# PSPS_AVNC_SRD_central-2020-10-12-2.net
KiCad netlist of a schematic drawn in EAGLE
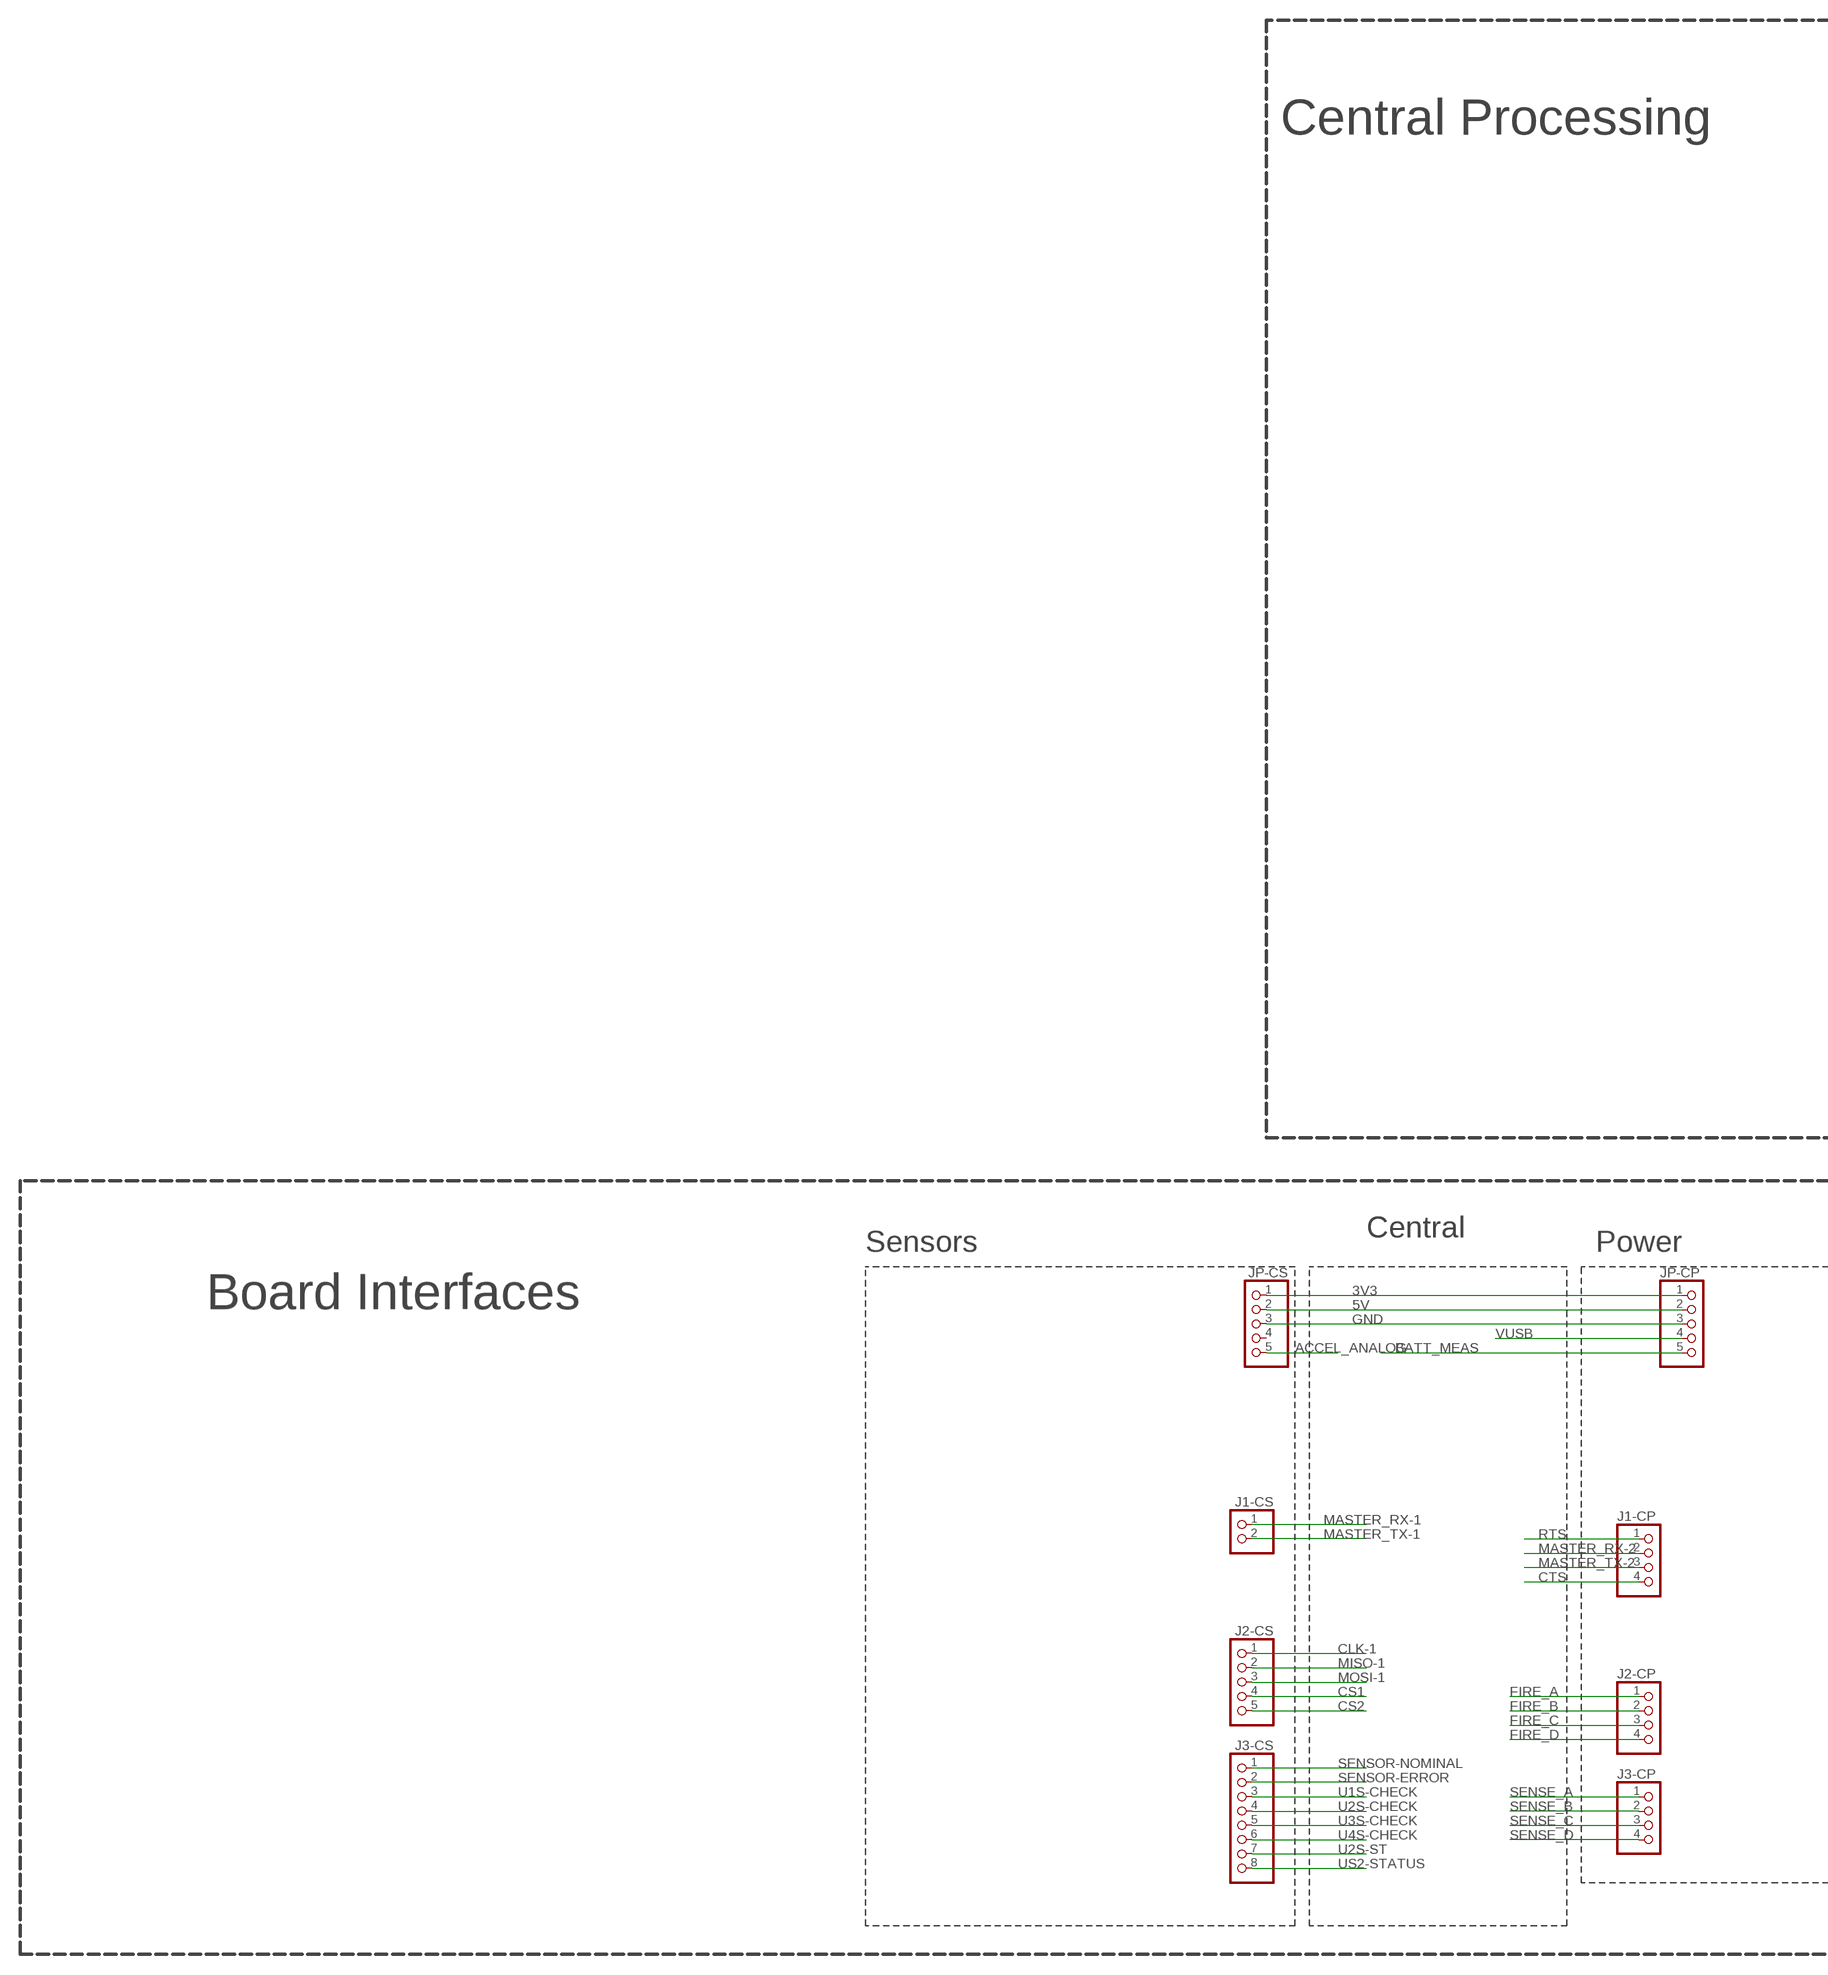
[diagram p0: schematic, sheet 1, part 1 of 2]
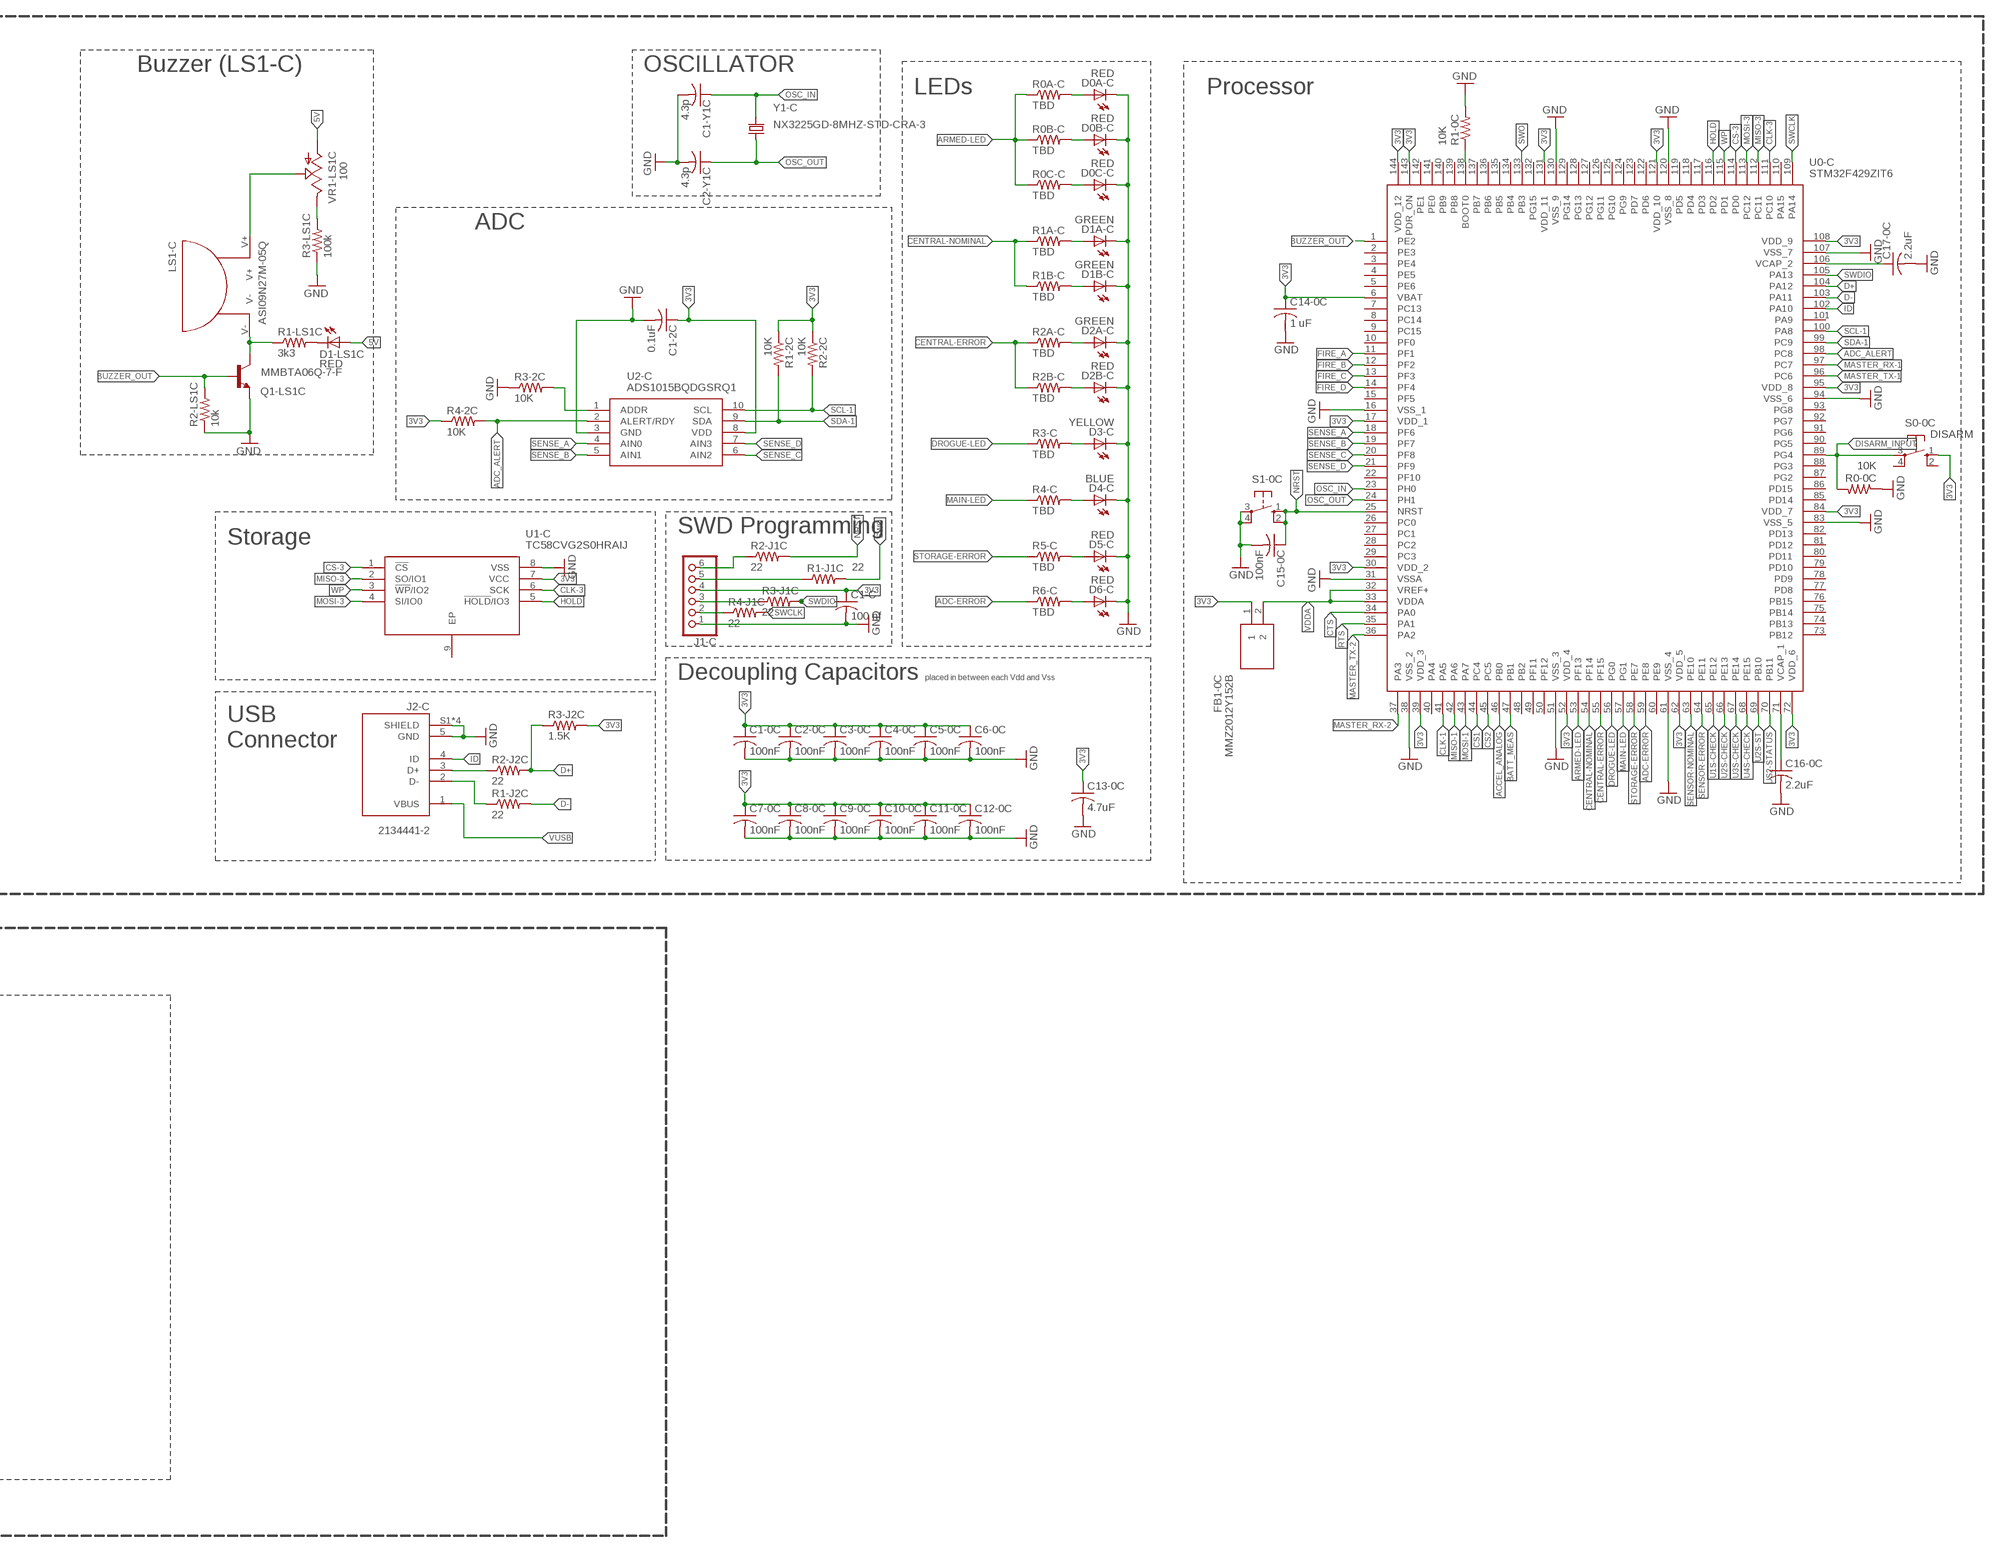
[diagram p1: schematic, sheet 1, part 2 of 2]

(export (version "E")
  (design (tool "Eeschema 10.0.6"))
  (components
    (comp (ref "C1-0C")
      (value "100nF")
      (footprint "eagle-import:C0805")
      (libsource (lib "eagle-import") (part "C-USC0805"))
    )
    (comp (ref "C1-2C")
      (value "0.1uF")
      (footprint "eagle-import:C0805")
      (libsource (lib "eagle-import") (part "C-USC0805"))
    )
    (comp (ref "C1-C")
      (value "100 nf")
      (footprint "eagle-import:C0805")
      (libsource (lib "eagle-import") (part "C-USC0805"))
    )
    (comp (ref "C1-Y1C")
      (value "4.3p")
      (footprint "eagle-import:C0805")
      (libsource (lib "eagle-import") (part "C-USC0805"))
    )
    (comp (ref "C2-0C")
      (value "100nF")
      (footprint "eagle-import:C0805")
      (libsource (lib "eagle-import") (part "C-USC0805"))
    )
    (comp (ref "C2-Y1C")
      (value "4.3p")
      (footprint "eagle-import:C0805")
      (libsource (lib "eagle-import") (part "C-USC0805"))
    )
    (comp (ref "C3-0C")
      (value "100nF")
      (footprint "eagle-import:C0805")
      (libsource (lib "eagle-import") (part "C-USC0805"))
    )
    (comp (ref "C4-0C")
      (value "100nF")
      (footprint "eagle-import:C0805")
      (libsource (lib "eagle-import") (part "C-USC0805"))
    )
    (comp (ref "C5-0C")
      (value "100nF")
      (footprint "eagle-import:C0805")
      (libsource (lib "eagle-import") (part "C-USC0805"))
    )
    (comp (ref "C6-0C")
      (value "100nF")
      (footprint "eagle-import:C0805")
      (libsource (lib "eagle-import") (part "C-USC0805"))
    )
    (comp (ref "C7-0C")
      (value "100nF")
      (footprint "eagle-import:C0805")
      (libsource (lib "eagle-import") (part "C-USC0805"))
    )
    (comp (ref "C8-0C")
      (value "100nF")
      (footprint "eagle-import:C0805")
      (libsource (lib "eagle-import") (part "C-USC0805"))
    )
    (comp (ref "C9-0C")
      (value "100nF")
      (footprint "eagle-import:C0805")
      (libsource (lib "eagle-import") (part "C-USC0805"))
    )
    (comp (ref "C10-0C")
      (value "100nF")
      (footprint "eagle-import:C0805")
      (libsource (lib "eagle-import") (part "C-USC0805"))
    )
    (comp (ref "C11-0C")
      (value "100nF")
      (footprint "eagle-import:C0805")
      (libsource (lib "eagle-import") (part "C-USC0805"))
    )
    (comp (ref "C12-0C")
      (value "100nF")
      (footprint "eagle-import:C0805")
      (libsource (lib "eagle-import") (part "C-USC0805"))
    )
    (comp (ref "C13-0C")
      (value "4.7uF")
      (footprint "eagle-import:C0805")
      (libsource (lib "eagle-import") (part "C-USC0805"))
    )
    (comp (ref "C14-0C")
      (value "1 uF")
      (footprint "eagle-import:C0805")
      (libsource (lib "eagle-import") (part "C-USC0805"))
    )
    (comp (ref "C15-0C")
      (value "100nF")
      (footprint "eagle-import:C0805")
      (libsource (lib "eagle-import") (part "C-USC0805"))
    )
    (comp (ref "C16-0C")
      (value "2.2uF")
      (footprint "eagle-import:C0805")
      (libsource (lib "eagle-import") (part "C-USC0805"))
    )
    (comp (ref "C17-0C")
      (value "2.2uF")
      (footprint "eagle-import:C0805")
      (libsource (lib "eagle-import") (part "C-USC0805"))
    )
    (comp (ref "D0A-C")
      (value "RED")
      (footprint "eagle-import:CHIPLED_0805")
      (libsource (lib "eagle-import") (part "LEDCHIPLED_0805"))
    )
    (comp (ref "D0B-C")
      (value "RED")
      (footprint "eagle-import:CHIPLED_0805")
      (libsource (lib "eagle-import") (part "LEDCHIPLED_0805"))
    )
    (comp (ref "D0C-C")
      (value "RED")
      (footprint "eagle-import:CHIPLED_0805")
      (libsource (lib "eagle-import") (part "LEDCHIPLED_0805"))
    )
    (comp (ref "D1-LS1C")
      (value "RED")
      (footprint "eagle-import:CHIPLED_0805")
      (libsource (lib "eagle-import") (part "LEDCHIPLED_0805"))
    )
    (comp (ref "D1A-C")
      (value "GREEN")
      (footprint "eagle-import:CHIPLED_0805")
      (libsource (lib "eagle-import") (part "LEDCHIPLED_0805"))
    )
    (comp (ref "D1B-C")
      (value "GREEN")
      (footprint "eagle-import:CHIPLED_0805")
      (libsource (lib "eagle-import") (part "LEDCHIPLED_0805"))
    )
    (comp (ref "D2A-C")
      (value "GREEN")
      (footprint "eagle-import:CHIPLED_0805")
      (libsource (lib "eagle-import") (part "LEDCHIPLED_0805"))
    )
    (comp (ref "D2B-C")
      (value "RED")
      (footprint "eagle-import:CHIPLED_0805")
      (libsource (lib "eagle-import") (part "LEDCHIPLED_0805"))
    )
    (comp (ref "D3-C")
      (value "YELLOW")
      (footprint "eagle-import:CHIPLED_0805")
      (libsource (lib "eagle-import") (part "LEDCHIPLED_0805"))
    )
    (comp (ref "D4-C")
      (value "BLUE")
      (footprint "eagle-import:CHIPLED_0805")
      (libsource (lib "eagle-import") (part "LEDCHIPLED_0805"))
    )
    (comp (ref "D5-C")
      (value "RED")
      (footprint "eagle-import:CHIPLED_0805")
      (libsource (lib "eagle-import") (part "LEDCHIPLED_0805"))
    )
    (comp (ref "D6-C")
      (value "RED")
      (footprint "eagle-import:CHIPLED_0805")
      (libsource (lib "eagle-import") (part "LEDCHIPLED_0805"))
    )
    (comp (ref "FB1-0C")
      (value "MMZ2012Y152B")
      (footprint "eagle-import:BEADC2012X105N")
      (fields (field (name "MOUSER_PART_NUMBER") "810-MMZ2012Y152B"))
      (libsource (lib "eagle-import") (part "MMZ2012Y152B"))
    )
    (comp (ref "J1-C")
      (value "PINHD-1X6")
      (footprint "eagle-import:1X06")
      (libsource (lib "eagle-import") (part "PINHD-1X6"))
    )
    (comp (ref "J1-CP")
      (value "PINHD-1X4")
      (footprint "eagle-import:1X04")
      (libsource (lib "eagle-import") (part "PINHD-1X4"))
    )
    (comp (ref "J1-CS")
      (value "PINHD-1X2")
      (footprint "eagle-import:1X02")
      (libsource (lib "eagle-import") (part "PINHD-1X2"))
    )
    (comp (ref "J2-C")
      (value "2134441-2")
      (footprint "eagle-import:TE_2134441-2")
      (fields (field (name "DIGI-KEY_PART_NUMBER") "A118104CT-ND") (field (name "MF") "TE Connectivity"))
      (libsource (lib "eagle-import") (part "2134441-2"))
    )
    (comp (ref "J2-CP")
      (value "PINHD-1X4")
      (footprint "eagle-import:1X04")
      (libsource (lib "eagle-import") (part "PINHD-1X4"))
    )
    (comp (ref "J2-CS")
      (value "PINHD-1X5")
      (footprint "eagle-import:1X05")
      (libsource (lib "eagle-import") (part "PINHD-1X5"))
    )
    (comp (ref "J3-CP")
      (value "PINHD-1X4")
      (footprint "eagle-import:1X04")
      (libsource (lib "eagle-import") (part "PINHD-1X4"))
    )
    (comp (ref "J3-CS")
      (value "PINHD-1X8")
      (footprint "eagle-import:1X08")
      (libsource (lib "eagle-import") (part "PINHD-1X8"))
    )
    (comp (ref "JP-CP")
      (value "PINHD-1X5")
      (footprint "eagle-import:1X05")
      (libsource (lib "eagle-import") (part "PINHD-1X5"))
    )
    (comp (ref "JP-CS")
      (value "PINHD-1X5")
      (footprint "eagle-import:1X05")
      (libsource (lib "eagle-import") (part "PINHD-1X5"))
    )
    (comp (ref "LS1-C")
      (value "ASI09N27M-05Q")
      (footprint "eagle-import:ASI09N27M-05Q")
      (libsource (lib "eagle-import") (part "ASI09N27M-05Q"))
    )
    (comp (ref "Q1-LS1C")
      (value "MMBTA06Q-7-F")
      (footprint "eagle-import:SOT23")
      (libsource (lib "eagle-import") (part "NPN_TRANSISTOR"))
    )
    (comp (ref "R0-0C")
      (value "10K")
      (footprint "eagle-import:R0805")
      (libsource (lib "eagle-import") (part "R-US_R0805"))
    )
    (comp (ref "R0A-C")
      (value "TBD")
      (footprint "eagle-import:M0805")
      (libsource (lib "eagle-import") (part "R-US_M0805"))
    )
    (comp (ref "R0B-C")
      (value "TBD")
      (footprint "eagle-import:M0805")
      (libsource (lib "eagle-import") (part "R-US_M0805"))
    )
    (comp (ref "R0C-C")
      (value "TBD")
      (footprint "eagle-import:M0805")
      (libsource (lib "eagle-import") (part "R-US_M0805"))
    )
    (comp (ref "R1-0C")
      (value "10K")
      (footprint "eagle-import:R0805")
      (libsource (lib "eagle-import") (part "R-US_R0805"))
    )
    (comp (ref "R1-2C")
      (value "10K")
      (footprint "eagle-import:R0805")
      (libsource (lib "eagle-import") (part "R-US_R0805"))
    )
    (comp (ref "R1-J1C")
      (value "22")
      (footprint "eagle-import:M0805")
      (libsource (lib "eagle-import") (part "R-US_M0805"))
    )
    (comp (ref "R1-J2C")
      (value "22")
      (footprint "eagle-import:M0805")
      (libsource (lib "eagle-import") (part "R-US_M0805"))
    )
    (comp (ref "R1-LS1C")
      (value "3k3")
      (footprint "eagle-import:R0805")
      (libsource (lib "eagle-import") (part "resistor_348_R-US_R0805"))
    )
    (comp (ref "R1A-C")
      (value "TBD")
      (footprint "eagle-import:M0805")
      (libsource (lib "eagle-import") (part "R-US_M0805"))
    )
    (comp (ref "R1B-C")
      (value "TBD")
      (footprint "eagle-import:M0805")
      (libsource (lib "eagle-import") (part "R-US_M0805"))
    )
    (comp (ref "R2-2C")
      (value "10K")
      (footprint "eagle-import:R0805")
      (libsource (lib "eagle-import") (part "R-US_R0805"))
    )
    (comp (ref "R2-J1C")
      (value "22")
      (footprint "eagle-import:M0805")
      (libsource (lib "eagle-import") (part "R-US_M0805"))
    )
    (comp (ref "R2-J2C")
      (value "22")
      (footprint "eagle-import:M0805")
      (libsource (lib "eagle-import") (part "R-US_M0805"))
    )
    (comp (ref "R2-LS1C")
      (value "10k")
      (footprint "eagle-import:R0805")
      (libsource (lib "eagle-import") (part "resistor_348_R-US_R0805"))
    )
    (comp (ref "R2A-C")
      (value "TBD")
      (footprint "eagle-import:M0805")
      (libsource (lib "eagle-import") (part "R-US_M0805"))
    )
    (comp (ref "R2B-C")
      (value "TBD")
      (footprint "eagle-import:M0805")
      (libsource (lib "eagle-import") (part "R-US_M0805"))
    )
    (comp (ref "R3-2C")
      (value "10K")
      (footprint "eagle-import:R0805")
      (libsource (lib "eagle-import") (part "R-US_R0805"))
    )
    (comp (ref "R3-C")
      (value "TBD")
      (footprint "eagle-import:M0805")
      (libsource (lib "eagle-import") (part "R-US_M0805"))
    )
    (comp (ref "R3-J1C")
      (value "22")
      (footprint "eagle-import:M0805")
      (libsource (lib "eagle-import") (part "R-US_M0805"))
    )
    (comp (ref "R3-J2C")
      (value "1.5K")
      (footprint "eagle-import:M0805")
      (libsource (lib "eagle-import") (part "R-US_M0805"))
    )
    (comp (ref "R3-LS1C")
      (value "100k")
      (footprint "eagle-import:R0805")
      (libsource (lib "eagle-import") (part "resistor_348_R-US_R0805"))
    )
    (comp (ref "R4-2C")
      (value "10K")
      (footprint "eagle-import:R0805")
      (libsource (lib "eagle-import") (part "R-US_R0805"))
    )
    (comp (ref "R4-C")
      (value "TBD")
      (footprint "eagle-import:M0805")
      (libsource (lib "eagle-import") (part "R-US_M0805"))
    )
    (comp (ref "R4-J1C")
      (value "22")
      (footprint "eagle-import:M0805")
      (libsource (lib "eagle-import") (part "R-US_M0805"))
    )
    (comp (ref "R5-C")
      (value "TBD")
      (footprint "eagle-import:M0805")
      (libsource (lib "eagle-import") (part "R-US_M0805"))
    )
    (comp (ref "R6-C")
      (value "TBD")
      (footprint "eagle-import:M0805")
      (libsource (lib "eagle-import") (part "R-US_M0805"))
    )
    (comp (ref "S0-0C")
      (value "DISARM")
      (footprint "eagle-import:B3F-10XX")
      (fields (field (name "MPN") "B3F-1000"))
      (libsource (lib "eagle-import") (part "10-XX"))
    )
    (comp (ref "S1-0C")
      (value "10-XX")
      (footprint "eagle-import:B3F-10XX")
      (fields (field (name "MPN") "B3F-1000"))
      (libsource (lib "eagle-import") (part "10-XX"))
    )
    (comp (ref "U0-C")
      (value "STM32F429ZIT6")
      (footprint "eagle-import:QFP50P2200X2200X160-144N")
      (fields (field (name "MOUSER_PART_NUMBER") "511-STM32F429ZIT6"))
      (libsource (lib "eagle-import") (part "STM32F429ZIT6"))
    )
    (comp (ref "U1-C")
      (value "TC58CVG2S0HRAIJ")
      (footprint "eagle-import:SON127P800X600X80-9N")
      (fields (field (name "MOUSER_PART_NUMBER") "757-TC58CVG2S0HRAIJ"))
      (libsource (lib "eagle-import") (part "TC58CVG2S0HRAIJ"))
    )
    (comp (ref "U2-C")
      (value "ADS1015BQDGSRQ1")
      (footprint "eagle-import:SOP50P490X110-10N")
      (fields (field (name "MOUSER_PART_NUMBER") "595-ADS1015BQDGSRQ1"))
      (libsource (lib "eagle-import") (part "ADS1015BQDGSRQ1"))
    )
    (comp (ref "VR1-LS1C")
      (value "100")
      (footprint "eagle-import:LI10")
      (libsource (lib "eagle-import") (part "TRIM_US-LI10"))
    )
    (comp (ref "Y1-C")
      (value "NX3225GD-8MHZ-STD-CRA-3")
      (footprint "eagle-import:NX3225GD")
      (libsource (lib "eagle-import") (part "NX3225GD"))
    )
  )
  (nets
    (net (code "1") (name "3V3") (class "Default")
      (node (ref "C1-0C") (pin "1") (pinfunction "1_1") (pintype "passive"))
      (node (ref "C1-2C") (pin "1") (pinfunction "1_1") (pintype "passive"))
      (node (ref "C1-C") (pin "1") (pinfunction "1_1") (pintype "passive"))
      (node (ref "C10-0C") (pin "1") (pinfunction "1_1") (pintype "passive"))
      (node (ref "C11-0C") (pin "1") (pinfunction "1_1") (pintype "passive"))
      (node (ref "C12-0C") (pin "1") (pinfunction "1_1") (pintype "passive"))
      (node (ref "C13-0C") (pin "1") (pinfunction "1_1") (pintype "passive"))
      (node (ref "C14-0C") (pin "1") (pinfunction "1_1") (pintype "passive"))
      (node (ref "C2-0C") (pin "1") (pinfunction "1_1") (pintype "passive"))
      (node (ref "C3-0C") (pin "1") (pinfunction "1_1") (pintype "passive"))
      (node (ref "C4-0C") (pin "1") (pinfunction "1_1") (pintype "passive"))
      (node (ref "C5-0C") (pin "1") (pinfunction "1_1") (pintype "passive"))
      (node (ref "C6-0C") (pin "1") (pinfunction "1_1") (pintype "passive"))
      (node (ref "C7-0C") (pin "1") (pinfunction "1_1") (pintype "passive"))
      (node (ref "C8-0C") (pin "1") (pinfunction "1_1") (pintype "passive"))
      (node (ref "C9-0C") (pin "1") (pinfunction "1_1") (pintype "passive"))
      (node (ref "FB1-0C") (pin "1") (pinfunction "1_1") (pintype "bidirectional"))
      (node (ref "J1-C") (pin "4") (pinfunction "4_4") (pintype "passive"))
      (node (ref "JP-CP") (pin "1") (pinfunction "1_1") (pintype "passive"))
      (node (ref "JP-CS") (pin "1") (pinfunction "1_1") (pintype "passive"))
      (node (ref "R1-2C") (pin "1") (pinfunction "1_1") (pintype "passive"))
      (node (ref "R2-2C") (pin "1") (pinfunction "1_1") (pintype "passive"))
      (node (ref "R3-J2C") (pin "2") (pinfunction "2_2") (pintype "passive"))
      (node (ref "R4-2C") (pin "1") (pinfunction "1_1") (pintype "passive"))
      (node (ref "S0-0C") (pin "1") (pinfunction "S_1") (pintype "passive"))
      (node (ref "U0-C") (pin "108") (pinfunction "VDD_9_108") (pintype "power_in"))
      (node (ref "U0-C") (pin "121") (pinfunction "VDD_10_121") (pintype "power_in"))
      (node (ref "U0-C") (pin "131") (pinfunction "VDD_11_131") (pintype "power_in"))
      (node (ref "U0-C") (pin "143") (pinfunction "PDR_ON_143") (pintype "bidirectional"))
      (node (ref "U0-C") (pin "144") (pinfunction "VDD_12_144") (pintype "power_in"))
      (node (ref "U0-C") (pin "17") (pinfunction "VDD_1_17") (pintype "power_in"))
      (node (ref "U0-C") (pin "30") (pinfunction "VDD_2_30") (pintype "power_in"))
      (node (ref "U0-C") (pin "39") (pinfunction "VDD_3_39") (pintype "power_in"))
      (node (ref "U0-C") (pin "52") (pinfunction "VDD_4_52") (pintype "power_in"))
      (node (ref "U0-C") (pin "6") (pinfunction "VBAT_6") (pintype "bidirectional"))
      (node (ref "U0-C") (pin "62") (pinfunction "VDD_5_62") (pintype "power_in"))
      (node (ref "U0-C") (pin "72") (pinfunction "VDD_6_72") (pintype "power_in"))
      (node (ref "U0-C") (pin "84") (pinfunction "VDD_7_84") (pintype "power_in"))
      (node (ref "U0-C") (pin "95") (pinfunction "VDD_8_95") (pintype "power_in"))
      (node (ref "U1-C") (pin "7") (pinfunction "VCC_7") (pintype "bidirectional"))
      (node (ref "U2-C") (pin "8") (pinfunction "VDD_8") (pintype "bidirectional"))
    )
    (net (code "2") (name "5V") (class "Default")
      (node (ref "D1-LS1C") (pin "A") (pinfunction "A_A") (pintype "passive"))
      (node (ref "JP-CP") (pin "2") (pinfunction "2_2") (pintype "passive"))
      (node (ref "JP-CS") (pin "2") (pinfunction "2_2") (pintype "passive"))
      (node (ref "VR1-LS1C") (pin "A") (pinfunction "A_A") (pintype "passive"))
    )
    (net (code "3") (name "ACCEL_ANALOG") (class "Default")
      (node (ref "JP-CS") (pin "5") (pinfunction "5_5") (pintype "passive"))
      (node (ref "U0-C") (pin "46") (pinfunction "PB0_46") (pintype "bidirectional"))
    )
    (net (code "4") (name "ADC-ERROR") (class "Default")
      (node (ref "R6-C") (pin "1") (pinfunction "1_1") (pintype "passive"))
      (node (ref "U0-C") (pin "59") (pinfunction "PE8_59") (pintype "bidirectional"))
    )
    (net (code "5") (name "ADC_ALERT") (class "Default")
      (node (ref "R4-2C") (pin "2") (pinfunction "2_2") (pintype "passive"))
      (node (ref "U0-C") (pin "98") (pinfunction "PC8_98") (pintype "bidirectional"))
      (node (ref "U2-C") (pin "2") (pinfunction "ALERT/RDY_2") (pintype "bidirectional"))
    )
    (net (code "6") (name "ARMED-LED") (class "Default")
      (node (ref "R0A-C") (pin "1") (pinfunction "1_1") (pintype "passive"))
      (node (ref "R0B-C") (pin "1") (pinfunction "1_1") (pintype "passive"))
      (node (ref "R0C-C") (pin "1") (pinfunction "1_1") (pintype "passive"))
      (node (ref "U0-C") (pin "53") (pinfunction "PF13_53") (pintype "bidirectional"))
    )
    (net (code "7") (name "BATT_MEAS") (class "Default")
      (node (ref "JP-CP") (pin "5") (pinfunction "5_5") (pintype "passive"))
      (node (ref "U0-C") (pin "47") (pinfunction "PB1_47") (pintype "bidirectional"))
    )
    (net (code "8") (name "BUZZER_OUT") (class "Default")
      (node (ref "Q1-LS1C") (pin "1") (pinfunction "B_1") (pintype "passive"))
      (node (ref "R2-LS1C") (pin "2") (pinfunction "2_2") (pintype "passive"))
      (node (ref "U0-C") (pin "1") (pinfunction "PE2_1") (pintype "bidirectional"))
    )
    (net (code "9") (name "CENTRAL-ERROR") (class "Default")
      (node (ref "R2A-C") (pin "1") (pinfunction "1_1") (pintype "passive"))
      (node (ref "R2B-C") (pin "1") (pinfunction "1_1") (pintype "passive"))
      (node (ref "U0-C") (pin "55") (pinfunction "PF15_55") (pintype "bidirectional"))
    )
    (net (code "10") (name "CENTRAL-NOMINAL") (class "Default")
      (node (ref "R1A-C") (pin "1") (pinfunction "1_1") (pintype "passive"))
      (node (ref "R1B-C") (pin "1") (pinfunction "1_1") (pintype "passive"))
      (node (ref "U0-C") (pin "54") (pinfunction "PF14_54") (pintype "bidirectional"))
    )
    (net (code "11") (name "CLK-1") (class "Default")
      (node (ref "J2-CS") (pin "1") (pinfunction "1_1") (pintype "passive"))
      (node (ref "U0-C") (pin "41") (pinfunction "PA5_41") (pintype "bidirectional"))
    )
    (net (code "12") (name "CLK-3") (class "Default")
      (node (ref "U0-C") (pin "111") (pinfunction "PC10_111") (pintype "bidirectional"))
      (node (ref "U1-C") (pin "6") (pinfunction "SCK_6") (pintype "bidirectional"))
    )
    (net (code "13") (name "CS-3") (class "Default")
      (node (ref "U0-C") (pin "114") (pinfunction "PD0_114") (pintype "bidirectional"))
      (node (ref "U1-C") (pin "1") (pinfunction "~{CS}_1") (pintype "bidirectional"))
    )
    (net (code "14") (name "CS1") (class "Default")
      (node (ref "J2-CS") (pin "4") (pinfunction "4_4") (pintype "passive"))
      (node (ref "U0-C") (pin "44") (pinfunction "PC4_44") (pintype "bidirectional"))
    )
    (net (code "15") (name "CS2") (class "Default")
      (node (ref "J2-CS") (pin "5") (pinfunction "5_5") (pintype "passive"))
      (node (ref "U0-C") (pin "45") (pinfunction "PC5_45") (pintype "bidirectional"))
    )
    (net (code "16") (name "CTS") (class "Default")
      (node (ref "J1-CP") (pin "4") (pinfunction "4_4") (pintype "passive"))
      (node (ref "U0-C") (pin "34") (pinfunction "PA0_34") (pintype "bidirectional"))
    )
    (net (code "17") (name "D+") (class "Default")
      (node (ref "R2-J2C") (pin "2") (pinfunction "2_2") (pintype "passive"))
      (node (ref "R3-J2C") (pin "1") (pinfunction "1_1") (pintype "passive"))
      (node (ref "U0-C") (pin "104") (pinfunction "PA12_104") (pintype "bidirectional"))
    )
    (net (code "18") (name "D-") (class "Default")
      (node (ref "R1-J2C") (pin "2") (pinfunction "2_2") (pintype "passive"))
      (node (ref "U0-C") (pin "103") (pinfunction "PA11_103") (pintype "bidirectional"))
    )
    (net (code "19") (name "DISARM_INPUT") (class "Default")
      (node (ref "R0-0C") (pin "2") (pinfunction "2_2") (pintype "passive"))
      (node (ref "S0-0C") (pin "3") (pinfunction "P_3") (pintype "passive"))
      (node (ref "U0-C") (pin "89") (pinfunction "PG4_89") (pintype "bidirectional"))
    )
    (net (code "20") (name "DROGUE-LED") (class "Default")
      (node (ref "R3-C") (pin "1") (pinfunction "1_1") (pintype "passive"))
      (node (ref "U0-C") (pin "56") (pinfunction "PG0_56") (pintype "bidirectional"))
    )
    (net (code "21") (name "FIRE_A") (class "Default")
      (node (ref "J2-CP") (pin "1") (pinfunction "1_1") (pintype "passive"))
      (node (ref "U0-C") (pin "11") (pinfunction "PF1_11") (pintype "bidirectional"))
    )
    (net (code "22") (name "FIRE_B") (class "Default")
      (node (ref "J2-CP") (pin "2") (pinfunction "2_2") (pintype "passive"))
      (node (ref "U0-C") (pin "12") (pinfunction "PF2_12") (pintype "bidirectional"))
    )
    (net (code "23") (name "FIRE_C") (class "Default")
      (node (ref "J2-CP") (pin "3") (pinfunction "3_3") (pintype "passive"))
      (node (ref "U0-C") (pin "13") (pinfunction "PF3_13") (pintype "bidirectional"))
    )
    (net (code "24") (name "FIRE_D") (class "Default")
      (node (ref "J2-CP") (pin "4") (pinfunction "4_4") (pintype "passive"))
      (node (ref "U0-C") (pin "14") (pinfunction "PF4_14") (pintype "bidirectional"))
    )
    (net (code "25") (name "GND") (class "Default")
      (node (ref "C1-0C") (pin "2") (pinfunction "2_2") (pintype "passive"))
      (node (ref "C1-2C") (pin "2") (pinfunction "2_2") (pintype "passive"))
      (node (ref "C1-C") (pin "2") (pinfunction "2_2") (pintype "passive"))
      (node (ref "C1-Y1C") (pin "2") (pinfunction "2_2") (pintype "passive"))
      (node (ref "C10-0C") (pin "2") (pinfunction "2_2") (pintype "passive"))
      (node (ref "C11-0C") (pin "2") (pinfunction "2_2") (pintype "passive"))
      (node (ref "C12-0C") (pin "2") (pinfunction "2_2") (pintype "passive"))
      (node (ref "C13-0C") (pin "2") (pinfunction "2_2") (pintype "passive"))
      (node (ref "C14-0C") (pin "2") (pinfunction "2_2") (pintype "passive"))
      (node (ref "C15-0C") (pin "2") (pinfunction "2_2") (pintype "passive"))
      (node (ref "C16-0C") (pin "2") (pinfunction "2_2") (pintype "passive"))
      (node (ref "C17-0C") (pin "2") (pinfunction "2_2") (pintype "passive"))
      (node (ref "C2-0C") (pin "2") (pinfunction "2_2") (pintype "passive"))
      (node (ref "C2-Y1C") (pin "2") (pinfunction "2_2") (pintype "passive"))
      (node (ref "C3-0C") (pin "2") (pinfunction "2_2") (pintype "passive"))
      (node (ref "C4-0C") (pin "2") (pinfunction "2_2") (pintype "passive"))
      (node (ref "C5-0C") (pin "2") (pinfunction "2_2") (pintype "passive"))
      (node (ref "C6-0C") (pin "2") (pinfunction "2_2") (pintype "passive"))
      (node (ref "C7-0C") (pin "2") (pinfunction "2_2") (pintype "passive"))
      (node (ref "C8-0C") (pin "2") (pinfunction "2_2") (pintype "passive"))
      (node (ref "C9-0C") (pin "2") (pinfunction "2_2") (pintype "passive"))
      (node (ref "D0A-C") (pin "C") (pinfunction "C_C") (pintype "passive"))
      (node (ref "D0B-C") (pin "C") (pinfunction "C_C") (pintype "passive"))
      (node (ref "D0C-C") (pin "C") (pinfunction "C_C") (pintype "passive"))
      (node (ref "D1A-C") (pin "C") (pinfunction "C_C") (pintype "passive"))
      (node (ref "D1B-C") (pin "C") (pinfunction "C_C") (pintype "passive"))
      (node (ref "D2A-C") (pin "C") (pinfunction "C_C") (pintype "passive"))
      (node (ref "D2B-C") (pin "C") (pinfunction "C_C") (pintype "passive"))
      (node (ref "D3-C") (pin "C") (pinfunction "C_C") (pintype "passive"))
      (node (ref "D4-C") (pin "C") (pinfunction "C_C") (pintype "passive"))
      (node (ref "D5-C") (pin "C") (pinfunction "C_C") (pintype "passive"))
      (node (ref "D6-C") (pin "C") (pinfunction "C_C") (pintype "passive"))
      (node (ref "J1-C") (pin "1") (pinfunction "1_1") (pintype "passive"))
      (node (ref "J2-C") (pin "5") (pinfunction "GND_5") (pintype "power_in"))
      (node (ref "J2-C") (pin "S1") (pinfunction "SHIELD_S1") (pintype "power_in"))
      (node (ref "J2-C") (pin "S2") (pinfunction "SHIELD_S2") (pintype "power_in"))
      (node (ref "J2-C") (pin "S3") (pinfunction "SHIELD_S3") (pintype "power_in"))
      (node (ref "J2-C") (pin "S4") (pinfunction "SHIELD_S4") (pintype "power_in"))
      (node (ref "JP-CP") (pin "3") (pinfunction "3_3") (pintype "passive"))
      (node (ref "JP-CS") (pin "3") (pinfunction "3_3") (pintype "passive"))
      (node (ref "Q1-LS1C") (pin "3") (pinfunction "E_3") (pintype "passive"))
      (node (ref "R0-0C") (pin "1") (pinfunction "1_1") (pintype "passive"))
      (node (ref "R1-0C") (pin "2") (pinfunction "2_2") (pintype "passive"))
      (node (ref "R2-LS1C") (pin "1") (pinfunction "1_1") (pintype "passive"))
      (node (ref "R3-2C") (pin "1") (pinfunction "1_1") (pintype "passive"))
      (node (ref "R3-LS1C") (pin "1") (pinfunction "1_1") (pintype "passive"))
      (node (ref "S1-0C") (pin "3") (pinfunction "P_3") (pintype "passive"))
      (node (ref "S1-0C") (pin "4") (pinfunction "P1_4") (pintype "passive"))
      (node (ref "U0-C") (pin "107") (pinfunction "VSS_7_107") (pintype "power_in"))
      (node (ref "U0-C") (pin "120") (pinfunction "VSS_8_120") (pintype "power_in"))
      (node (ref "U0-C") (pin "130") (pinfunction "VSS_9_130") (pintype "power_in"))
      (node (ref "U0-C") (pin "16") (pinfunction "VSS_1_16") (pintype "power_in"))
      (node (ref "U0-C") (pin "31") (pinfunction "VSSA_31") (pintype "power_in"))
      (node (ref "U0-C") (pin "38") (pinfunction "VSS_2_38") (pintype "power_in"))
      (node (ref "U0-C") (pin "51") (pinfunction "VSS_3_51") (pintype "power_in"))
      (node (ref "U0-C") (pin "61") (pinfunction "VSS_4_61") (pintype "power_in"))
      (node (ref "U0-C") (pin "83") (pinfunction "VSS_5_83") (pintype "power_in"))
      (node (ref "U0-C") (pin "94") (pinfunction "VSS_6_94") (pintype "power_in"))
      (node (ref "U1-C") (pin "8") (pinfunction "VSS_8") (pintype "bidirectional"))
      (node (ref "U2-C") (pin "3") (pinfunction "GND_3") (pintype "bidirectional"))
    )
    (net (code "26") (name "HOLD") (class "Default")
      (node (ref "U0-C") (pin "116") (pinfunction "PD2_116") (pintype "bidirectional"))
      (node (ref "U1-C") (pin "5") (pinfunction "~{HOLD}/IO3_5") (pintype "bidirectional"))
    )
    (net (code "27") (name "ID") (class "Default")
      (node (ref "J2-C") (pin "4") (pinfunction "ID_4") (pintype "bidirectional"))
      (node (ref "U0-C") (pin "102") (pinfunction "PA10_102") (pintype "bidirectional"))
    )
    (net (code "28") (name "MAIN-LED") (class "Default")
      (node (ref "R4-C") (pin "1") (pinfunction "1_1") (pintype "passive"))
      (node (ref "U0-C") (pin "57") (pinfunction "PG1_57") (pintype "bidirectional"))
    )
    (net (code "29") (name "MASTER_RX-1") (class "Default")
      (node (ref "J1-CS") (pin "1") (pinfunction "1_1") (pintype "passive"))
      (node (ref "U0-C") (pin "97") (pinfunction "PC7_97") (pintype "bidirectional"))
    )
    (net (code "30") (name "MASTER_RX-2") (class "Default")
      (node (ref "J1-CP") (pin "2") (pinfunction "2_2") (pintype "passive"))
      (node (ref "U0-C") (pin "37") (pinfunction "PA3_37") (pintype "bidirectional"))
    )
    (net (code "31") (name "MASTER_TX-1") (class "Default")
      (node (ref "J1-CS") (pin "2") (pinfunction "2_2") (pintype "passive"))
      (node (ref "U0-C") (pin "96") (pinfunction "PC6_96") (pintype "bidirectional"))
    )
    (net (code "32") (name "MASTER_TX-2") (class "Default")
      (node (ref "J1-CP") (pin "3") (pinfunction "3_3") (pintype "passive"))
      (node (ref "U0-C") (pin "36") (pinfunction "PA2_36") (pintype "bidirectional"))
    )
    (net (code "33") (name "MISO-1") (class "Default")
      (node (ref "J2-CS") (pin "2") (pinfunction "2_2") (pintype "passive"))
      (node (ref "U0-C") (pin "42") (pinfunction "PA6_42") (pintype "bidirectional"))
    )
    (net (code "34") (name "MISO-3") (class "Default")
      (node (ref "U0-C") (pin "112") (pinfunction "PC11_112") (pintype "bidirectional"))
      (node (ref "U1-C") (pin "2") (pinfunction "SO/IO1_2") (pintype "bidirectional"))
    )
    (net (code "35") (name "MOSI-1") (class "Default")
      (node (ref "J2-CS") (pin "3") (pinfunction "3_3") (pintype "passive"))
      (node (ref "U0-C") (pin "43") (pinfunction "PA7_43") (pintype "bidirectional"))
    )
    (net (code "36") (name "MOSI-3") (class "Default")
      (node (ref "U0-C") (pin "113") (pinfunction "PC12_113") (pintype "bidirectional"))
      (node (ref "U1-C") (pin "4") (pinfunction "SI/IO0_4") (pintype "bidirectional"))
    )
    (net (code "37") (name "NRST") (class "Default")
      (node (ref "C15-0C") (pin "1") (pinfunction "1_1") (pintype "passive"))
      (node (ref "R2-J1C") (pin "2") (pinfunction "2_2") (pintype "passive"))
      (node (ref "S1-0C") (pin "1") (pinfunction "S_1") (pintype "passive"))
      (node (ref "S1-0C") (pin "2") (pinfunction "S1_2") (pintype "passive"))
      (node (ref "U0-C") (pin "25") (pinfunction "NRST_25") (pintype "input"))
    )
    (net (code "38") (name "Net-(D0A-C-PadA)") (class "Default")
      (node (ref "D0A-C") (pin "A") (pinfunction "A_A") (pintype "passive"))
      (node (ref "R0A-C") (pin "2") (pinfunction "2_2") (pintype "passive"))
    )
    (net (code "39") (name "Net-(D0B-C-PadA)") (class "Default")
      (node (ref "D0B-C") (pin "A") (pinfunction "A_A") (pintype "passive"))
      (node (ref "R0B-C") (pin "2") (pinfunction "2_2") (pintype "passive"))
    )
    (net (code "40") (name "Net-(D0C-C-PadA)") (class "Default")
      (node (ref "D0C-C") (pin "A") (pinfunction "A_A") (pintype "passive"))
      (node (ref "R0C-C") (pin "2") (pinfunction "2_2") (pintype "passive"))
    )
    (net (code "41") (name "Net-(D1-LS1C-PadC)") (class "Default")
      (node (ref "D1-LS1C") (pin "C") (pinfunction "C_C") (pintype "passive"))
      (node (ref "R1-LS1C") (pin "2") (pinfunction "2_2") (pintype "passive"))
    )
    (net (code "42") (name "Net-(D1A-C-PadA)") (class "Default")
      (node (ref "D1A-C") (pin "A") (pinfunction "A_A") (pintype "passive"))
      (node (ref "R1A-C") (pin "2") (pinfunction "2_2") (pintype "passive"))
    )
    (net (code "43") (name "Net-(D1B-C-PadA)") (class "Default")
      (node (ref "D1B-C") (pin "A") (pinfunction "A_A") (pintype "passive"))
      (node (ref "R1B-C") (pin "2") (pinfunction "2_2") (pintype "passive"))
    )
    (net (code "44") (name "Net-(D2A-C-PadA)") (class "Default")
      (node (ref "D2A-C") (pin "A") (pinfunction "A_A") (pintype "passive"))
      (node (ref "R2A-C") (pin "2") (pinfunction "2_2") (pintype "passive"))
    )
    (net (code "45") (name "Net-(D2B-C-PadA)") (class "Default")
      (node (ref "D2B-C") (pin "A") (pinfunction "A_A") (pintype "passive"))
      (node (ref "R2B-C") (pin "2") (pinfunction "2_2") (pintype "passive"))
    )
    (net (code "46") (name "Net-(D3-C-PadA)") (class "Default")
      (node (ref "D3-C") (pin "A") (pinfunction "A_A") (pintype "passive"))
      (node (ref "R3-C") (pin "2") (pinfunction "2_2") (pintype "passive"))
    )
    (net (code "47") (name "Net-(D4-C-PadA)") (class "Default")
      (node (ref "D4-C") (pin "A") (pinfunction "A_A") (pintype "passive"))
      (node (ref "R4-C") (pin "2") (pinfunction "2_2") (pintype "passive"))
    )
    (net (code "48") (name "Net-(D5-C-PadA)") (class "Default")
      (node (ref "D5-C") (pin "A") (pinfunction "A_A") (pintype "passive"))
      (node (ref "R5-C") (pin "2") (pinfunction "2_2") (pintype "passive"))
    )
    (net (code "49") (name "Net-(D6-C-PadA)") (class "Default")
      (node (ref "D6-C") (pin "A") (pinfunction "A_A") (pintype "passive"))
      (node (ref "R6-C") (pin "2") (pinfunction "2_2") (pintype "passive"))
    )
    (net (code "50") (name "Net-(J1-C-Pad2)") (class "Default")
      (node (ref "J1-C") (pin "2") (pinfunction "2_2") (pintype "passive"))
      (node (ref "R4-J1C") (pin "1") (pinfunction "1_1") (pintype "passive"))
    )
    (net (code "51") (name "Net-(J1-C-Pad3)") (class "Default")
      (node (ref "J1-C") (pin "3") (pinfunction "3_3") (pintype "passive"))
      (node (ref "R3-J1C") (pin "1") (pinfunction "1_1") (pintype "passive"))
    )
    (net (code "52") (name "Net-(J1-C-Pad5)") (class "Default")
      (node (ref "J1-C") (pin "5") (pinfunction "5_5") (pintype "passive"))
      (node (ref "R1-J1C") (pin "1") (pinfunction "1_1") (pintype "passive"))
    )
    (net (code "53") (name "Net-(J1-C-Pad6)") (class "Default")
      (node (ref "J1-C") (pin "6") (pinfunction "6_6") (pintype "passive"))
      (node (ref "R2-J1C") (pin "1") (pinfunction "1_1") (pintype "passive"))
    )
    (net (code "54") (name "Net-(J2-C-D+)") (class "Default")
      (node (ref "J2-C") (pin "3") (pinfunction "D+_3") (pintype "bidirectional"))
      (node (ref "R2-J2C") (pin "1") (pinfunction "1_1") (pintype "passive"))
    )
    (net (code "55") (name "Net-(J2-C-D-)") (class "Default")
      (node (ref "J2-C") (pin "2") (pinfunction "D-_2") (pintype "bidirectional"))
      (node (ref "R1-J2C") (pin "1") (pinfunction "1_1") (pintype "passive"))
    )
    (net (code "56") (name "Net-(LS1-C-PadV+)") (class "Default")
      (node (ref "LS1-C") (pin "V+") (pinfunction "V+_V+") (pintype "bidirectional"))
      (node (ref "VR1-LS1C") (pin "S") (pinfunction "S_S") (pintype "passive"))
    )
    (net (code "57") (name "Net-(Q1-LS1C-C)") (class "Default")
      (node (ref "LS1-C") (pin "V-") (pinfunction "V-_V-") (pintype "bidirectional"))
      (node (ref "Q1-LS1C") (pin "2") (pinfunction "C_2") (pintype "passive"))
      (node (ref "R1-LS1C") (pin "1") (pinfunction "1_1") (pintype "passive"))
    )
    (net (code "58") (name "Net-(R3-LS1C-Pad2)") (class "Default")
      (node (ref "R3-LS1C") (pin "2") (pinfunction "2_2") (pintype "passive"))
      (node (ref "VR1-LS1C") (pin "E") (pinfunction "E_E") (pintype "passive"))
    )
    (net (code "59") (name "Net-(U0-C-BOOT0)") (class "Default")
      (node (ref "R1-0C") (pin "1") (pinfunction "1_1") (pintype "passive"))
      (node (ref "U0-C") (pin "138") (pinfunction "BOOT0_138") (pintype "bidirectional"))
    )
    (net (code "60") (name "Net-(U0-C-VCAP_1)") (class "Default")
      (node (ref "C16-0C") (pin "1") (pinfunction "1_1") (pintype "passive"))
      (node (ref "U0-C") (pin "71") (pinfunction "VCAP_1_71") (pintype "bidirectional"))
    )
    (net (code "61") (name "Net-(U0-C-VCAP_2)") (class "Default")
      (node (ref "C17-0C") (pin "1") (pinfunction "1_1") (pintype "passive"))
      (node (ref "U0-C") (pin "106") (pinfunction "VCAP_2_106") (pintype "bidirectional"))
    )
    (net (code "62") (name "Net-(U2-C-ADDR)") (class "Default")
      (node (ref "R3-2C") (pin "2") (pinfunction "2_2") (pintype "passive"))
      (node (ref "U2-C") (pin "1") (pinfunction "ADDR_1") (pintype "bidirectional"))
    )
    (net (code "63") (name "OSC_IN") (class "Default")
      (node (ref "C1-Y1C") (pin "1") (pinfunction "1_1") (pintype "passive"))
      (node (ref "U0-C") (pin "23") (pinfunction "PH0_23") (pintype "bidirectional"))
      (node (ref "Y1-C") (pin "P$2") (pinfunction "2_P$2") (pintype "passive"))
    )
    (net (code "64") (name "OSC_OUT") (class "Default")
      (node (ref "C2-Y1C") (pin "1") (pinfunction "1_1") (pintype "passive"))
      (node (ref "U0-C") (pin "24") (pinfunction "PH1_24") (pintype "bidirectional"))
      (node (ref "Y1-C") (pin "P$1") (pinfunction "1_P$1") (pintype "passive"))
    )
    (net (code "65") (name "RTS") (class "Default")
      (node (ref "J1-CP") (pin "1") (pinfunction "1_1") (pintype "passive"))
      (node (ref "U0-C") (pin "35") (pinfunction "PA1_35") (pintype "bidirectional"))
    )
    (net (code "66") (name "SCL-1") (class "Default")
      (node (ref "R2-2C") (pin "2") (pinfunction "2_2") (pintype "passive"))
      (node (ref "U0-C") (pin "100") (pinfunction "PA8_100") (pintype "bidirectional"))
      (node (ref "U2-C") (pin "10") (pinfunction "SCL_10") (pintype "bidirectional"))
    )
    (net (code "67") (name "SDA-1") (class "Default")
      (node (ref "R1-2C") (pin "2") (pinfunction "2_2") (pintype "passive"))
      (node (ref "U0-C") (pin "99") (pinfunction "PC9_99") (pintype "bidirectional"))
      (node (ref "U2-C") (pin "9") (pinfunction "SDA_9") (pintype "bidirectional"))
    )
    (net (code "68") (name "SENSE_A") (class "Default")
      (node (ref "J3-CP") (pin "1") (pinfunction "1_1") (pintype "passive"))
      (node (ref "U0-C") (pin "18") (pinfunction "PF6_18") (pintype "bidirectional"))
      (node (ref "U2-C") (pin "4") (pinfunction "AIN0_4") (pintype "bidirectional"))
    )
    (net (code "69") (name "SENSE_B") (class "Default")
      (node (ref "J3-CP") (pin "2") (pinfunction "2_2") (pintype "passive"))
      (node (ref "U0-C") (pin "19") (pinfunction "PF7_19") (pintype "bidirectional"))
      (node (ref "U2-C") (pin "5") (pinfunction "AIN1_5") (pintype "bidirectional"))
    )
    (net (code "70") (name "SENSE_C") (class "Default")
      (node (ref "J3-CP") (pin "3") (pinfunction "3_3") (pintype "passive"))
      (node (ref "U0-C") (pin "20") (pinfunction "PF8_20") (pintype "bidirectional"))
      (node (ref "U2-C") (pin "6") (pinfunction "AIN2_6") (pintype "bidirectional"))
    )
    (net (code "71") (name "SENSE_D") (class "Default")
      (node (ref "J3-CP") (pin "4") (pinfunction "4_4") (pintype "passive"))
      (node (ref "U0-C") (pin "21") (pinfunction "PF9_21") (pintype "bidirectional"))
      (node (ref "U2-C") (pin "7") (pinfunction "AIN3_7") (pintype "bidirectional"))
    )
    (net (code "72") (name "SENSOR-ERROR") (class "Default")
      (node (ref "J3-CS") (pin "2") (pinfunction "2_2") (pintype "passive"))
      (node (ref "U0-C") (pin "64") (pinfunction "PE11_64") (pintype "bidirectional"))
    )
    (net (code "73") (name "SENSOR-NOMINAL") (class "Default")
      (node (ref "J3-CS") (pin "1") (pinfunction "1_1") (pintype "passive"))
      (node (ref "U0-C") (pin "63") (pinfunction "PE10_63") (pintype "bidirectional"))
    )
    (net (code "74") (name "STORAGE-ERROR") (class "Default")
      (node (ref "R5-C") (pin "1") (pinfunction "1_1") (pintype "passive"))
      (node (ref "U0-C") (pin "58") (pinfunction "PE7_58") (pintype "bidirectional"))
    )
    (net (code "75") (name "SWCLK") (class "Default")
      (node (ref "R4-J1C") (pin "2") (pinfunction "2_2") (pintype "passive"))
      (node (ref "U0-C") (pin "109") (pinfunction "PA14_109") (pintype "bidirectional"))
    )
    (net (code "76") (name "SWDIO") (class "Default")
      (node (ref "R3-J1C") (pin "2") (pinfunction "2_2") (pintype "passive"))
      (node (ref "U0-C") (pin "105") (pinfunction "PA13_105") (pintype "bidirectional"))
    )
    (net (code "77") (name "SWO") (class "Default")
      (node (ref "R1-J1C") (pin "2") (pinfunction "2_2") (pintype "passive"))
      (node (ref "U0-C") (pin "133") (pinfunction "PB3_133") (pintype "bidirectional"))
    )
    (net (code "78") (name "U1S-CHECK") (class "Default")
      (node (ref "J3-CS") (pin "3") (pinfunction "3_3") (pintype "passive"))
      (node (ref "U0-C") (pin "65") (pinfunction "PE12_65") (pintype "bidirectional"))
    )
    (net (code "79") (name "U2S-CHECK") (class "Default")
      (node (ref "J3-CS") (pin "4") (pinfunction "4_4") (pintype "passive"))
      (node (ref "U0-C") (pin "66") (pinfunction "PE13_66") (pintype "bidirectional"))
    )
    (net (code "80") (name "U2S-ST") (class "Default")
      (node (ref "J3-CS") (pin "7") (pinfunction "7_7") (pintype "passive"))
      (node (ref "U0-C") (pin "69") (pinfunction "PB10_69") (pintype "bidirectional"))
    )
    (net (code "81") (name "U3S-CHECK") (class "Default")
      (node (ref "J3-CS") (pin "5") (pinfunction "5_5") (pintype "passive"))
      (node (ref "U0-C") (pin "67") (pinfunction "PE14_67") (pintype "bidirectional"))
    )
    (net (code "82") (name "U4S-CHECK") (class "Default")
      (node (ref "J3-CS") (pin "6") (pinfunction "6_6") (pintype "passive"))
      (node (ref "U0-C") (pin "68") (pinfunction "PE15_68") (pintype "bidirectional"))
    )
    (net (code "83") (name "US2-STATUS") (class "Default")
      (node (ref "J3-CS") (pin "8") (pinfunction "8_8") (pintype "passive"))
      (node (ref "U0-C") (pin "70") (pinfunction "PB11_70") (pintype "bidirectional"))
    )
    (net (code "84") (name "VDDA") (class "Default")
      (node (ref "FB1-0C") (pin "2") (pinfunction "2_2") (pintype "bidirectional"))
      (node (ref "U0-C") (pin "32") (pinfunction "VREF+_32") (pintype "input"))
      (node (ref "U0-C") (pin "33") (pinfunction "VDDA_33") (pintype "power_in"))
    )
    (net (code "85") (name "VUSB") (class "Default")
      (node (ref "J2-C") (pin "1") (pinfunction "VBUS_1") (pintype "power_in"))
      (node (ref "JP-CP") (pin "4") (pinfunction "4_4") (pintype "passive"))
    )
    (net (code "86") (name "WP") (class "Default")
      (node (ref "U0-C") (pin "115") (pinfunction "PD1_115") (pintype "bidirectional"))
      (node (ref "U1-C") (pin "3") (pinfunction "~{WP}/IO2_3") (pintype "bidirectional"))
    )
    (net (code "87") (name "unconnected-(JP-CS-Pad4)") (class "Default")
      (node (ref "JP-CS") (pin "4") (pinfunction "4_4") (pintype "passive"))
    )
    (net (code "88") (name "unconnected-(S0-0C-P1-Pad4)") (class "Default")
      (node (ref "S0-0C") (pin "4") (pinfunction "P1_4") (pintype "passive"))
    )
    (net (code "89") (name "unconnected-(S0-0C-S1-Pad2)") (class "Default")
      (node (ref "S0-0C") (pin "2") (pinfunction "S1_2") (pintype "passive"))
    )
    (net (code "90") (name "unconnected-(U0-C-PA4-Pad40)") (class "Default")
      (node (ref "U0-C") (pin "40") (pinfunction "PA4_40") (pintype "bidirectional"))
    )
    (net (code "91") (name "unconnected-(U0-C-PA9-Pad101)") (class "Default")
      (node (ref "U0-C") (pin "101") (pinfunction "PA9_101") (pintype "bidirectional"))
    )
    (net (code "92") (name "unconnected-(U0-C-PA15-Pad110)") (class "Default")
      (node (ref "U0-C") (pin "110") (pinfunction "PA15_110") (pintype "bidirectional"))
    )
    (net (code "93") (name "unconnected-(U0-C-PB2-Pad48)") (class "Default")
      (node (ref "U0-C") (pin "48") (pinfunction "PB2_48") (pintype "bidirectional"))
    )
    (net (code "94") (name "unconnected-(U0-C-PB4-Pad134)") (class "Default")
      (node (ref "U0-C") (pin "134") (pinfunction "PB4_134") (pintype "bidirectional"))
    )
    (net (code "95") (name "unconnected-(U0-C-PB5-Pad135)") (class "Default")
      (node (ref "U0-C") (pin "135") (pinfunction "PB5_135") (pintype "bidirectional"))
    )
    (net (code "96") (name "unconnected-(U0-C-PB6-Pad136)") (class "Default")
      (node (ref "U0-C") (pin "136") (pinfunction "PB6_136") (pintype "bidirectional"))
    )
    (net (code "97") (name "unconnected-(U0-C-PB7-Pad137)") (class "Default")
      (node (ref "U0-C") (pin "137") (pinfunction "PB7_137") (pintype "bidirectional"))
    )
    (net (code "98") (name "unconnected-(U0-C-PB8-Pad139)") (class "Default")
      (node (ref "U0-C") (pin "139") (pinfunction "PB8_139") (pintype "bidirectional"))
    )
    (net (code "99") (name "unconnected-(U0-C-PB9-Pad140)") (class "Default")
      (node (ref "U0-C") (pin "140") (pinfunction "PB9_140") (pintype "bidirectional"))
    )
    (net (code "100") (name "unconnected-(U0-C-PB12-Pad73)") (class "Default")
      (node (ref "U0-C") (pin "73") (pinfunction "PB12_73") (pintype "bidirectional"))
    )
    (net (code "101") (name "unconnected-(U0-C-PB13-Pad74)") (class "Default")
      (node (ref "U0-C") (pin "74") (pinfunction "PB13_74") (pintype "bidirectional"))
    )
    (net (code "102") (name "unconnected-(U0-C-PB14-Pad75)") (class "Default")
      (node (ref "U0-C") (pin "75") (pinfunction "PB14_75") (pintype "bidirectional"))
    )
    (net (code "103") (name "unconnected-(U0-C-PB15-Pad76)") (class "Default")
      (node (ref "U0-C") (pin "76") (pinfunction "PB15_76") (pintype "bidirectional"))
    )
    (net (code "104") (name "unconnected-(U0-C-PC0-Pad26)") (class "Default")
      (node (ref "U0-C") (pin "26") (pinfunction "PC0_26") (pintype "bidirectional"))
    )
    (net (code "105") (name "unconnected-(U0-C-PC1-Pad27)") (class "Default")
      (node (ref "U0-C") (pin "27") (pinfunction "PC1_27") (pintype "bidirectional"))
    )
    (net (code "106") (name "unconnected-(U0-C-PC2-Pad28)") (class "Default")
      (node (ref "U0-C") (pin "28") (pinfunction "PC2_28") (pintype "bidirectional"))
    )
    (net (code "107") (name "unconnected-(U0-C-PC3-Pad29)") (class "Default")
      (node (ref "U0-C") (pin "29") (pinfunction "PC3_29") (pintype "bidirectional"))
    )
    (net (code "108") (name "unconnected-(U0-C-PC13-Pad7)") (class "Default")
      (node (ref "U0-C") (pin "7") (pinfunction "PC13_7") (pintype "bidirectional"))
    )
    (net (code "109") (name "unconnected-(U0-C-PC14-Pad8)") (class "Default")
      (node (ref "U0-C") (pin "8") (pinfunction "PC14_8") (pintype "bidirectional"))
    )
    (net (code "110") (name "unconnected-(U0-C-PC15-Pad9)") (class "Default")
      (node (ref "U0-C") (pin "9") (pinfunction "PC15_9") (pintype "bidirectional"))
    )
    (net (code "111") (name "unconnected-(U0-C-PD3-Pad117)") (class "Default")
      (node (ref "U0-C") (pin "117") (pinfunction "PD3_117") (pintype "bidirectional"))
    )
    (net (code "112") (name "unconnected-(U0-C-PD4-Pad118)") (class "Default")
      (node (ref "U0-C") (pin "118") (pinfunction "PD4_118") (pintype "bidirectional"))
    )
    (net (code "113") (name "unconnected-(U0-C-PD5-Pad119)") (class "Default")
      (node (ref "U0-C") (pin "119") (pinfunction "PD5_119") (pintype "bidirectional"))
    )
    (net (code "114") (name "unconnected-(U0-C-PD6-Pad122)") (class "Default")
      (node (ref "U0-C") (pin "122") (pinfunction "PD6_122") (pintype "bidirectional"))
    )
    (net (code "115") (name "unconnected-(U0-C-PD7-Pad123)") (class "Default")
      (node (ref "U0-C") (pin "123") (pinfunction "PD7_123") (pintype "bidirectional"))
    )
    (net (code "116") (name "unconnected-(U0-C-PD8-Pad77)") (class "Default")
      (node (ref "U0-C") (pin "77") (pinfunction "PD8_77") (pintype "bidirectional"))
    )
    (net (code "117") (name "unconnected-(U0-C-PD9-Pad78)") (class "Default")
      (node (ref "U0-C") (pin "78") (pinfunction "PD9_78") (pintype "bidirectional"))
    )
    (net (code "118") (name "unconnected-(U0-C-PD10-Pad79)") (class "Default")
      (node (ref "U0-C") (pin "79") (pinfunction "PD10_79") (pintype "bidirectional"))
    )
    (net (code "119") (name "unconnected-(U0-C-PD11-Pad80)") (class "Default")
      (node (ref "U0-C") (pin "80") (pinfunction "PD11_80") (pintype "bidirectional"))
    )
    (net (code "120") (name "unconnected-(U0-C-PD12-Pad81)") (class "Default")
      (node (ref "U0-C") (pin "81") (pinfunction "PD12_81") (pintype "bidirectional"))
    )
    (net (code "121") (name "unconnected-(U0-C-PD13-Pad82)") (class "Default")
      (node (ref "U0-C") (pin "82") (pinfunction "PD13_82") (pintype "bidirectional"))
    )
    (net (code "122") (name "unconnected-(U0-C-PD14-Pad85)") (class "Default")
      (node (ref "U0-C") (pin "85") (pinfunction "PD14_85") (pintype "bidirectional"))
    )
    (net (code "123") (name "unconnected-(U0-C-PD15-Pad86)") (class "Default")
      (node (ref "U0-C") (pin "86") (pinfunction "PD15_86") (pintype "bidirectional"))
    )
    (net (code "124") (name "unconnected-(U0-C-PE0-Pad141)") (class "Default")
      (node (ref "U0-C") (pin "141") (pinfunction "PE0_141") (pintype "bidirectional"))
    )
    (net (code "125") (name "unconnected-(U0-C-PE1-Pad142)") (class "Default")
      (node (ref "U0-C") (pin "142") (pinfunction "PE1_142") (pintype "bidirectional"))
    )
    (net (code "126") (name "unconnected-(U0-C-PE3-Pad2)") (class "Default")
      (node (ref "U0-C") (pin "2") (pinfunction "PE3_2") (pintype "bidirectional"))
    )
    (net (code "127") (name "unconnected-(U0-C-PE4-Pad3)") (class "Default")
      (node (ref "U0-C") (pin "3") (pinfunction "PE4_3") (pintype "bidirectional"))
    )
    (net (code "128") (name "unconnected-(U0-C-PE5-Pad4)") (class "Default")
      (node (ref "U0-C") (pin "4") (pinfunction "PE5_4") (pintype "bidirectional"))
    )
    (net (code "129") (name "unconnected-(U0-C-PE6-Pad5)") (class "Default")
      (node (ref "U0-C") (pin "5") (pinfunction "PE6_5") (pintype "bidirectional"))
    )
    (net (code "130") (name "unconnected-(U0-C-PE9-Pad60)") (class "Default")
      (node (ref "U0-C") (pin "60") (pinfunction "PE9_60") (pintype "bidirectional"))
    )
    (net (code "131") (name "unconnected-(U0-C-PF0-Pad10)") (class "Default")
      (node (ref "U0-C") (pin "10") (pinfunction "PF0_10") (pintype "bidirectional"))
    )
    (net (code "132") (name "unconnected-(U0-C-PF5-Pad15)") (class "Default")
      (node (ref "U0-C") (pin "15") (pinfunction "PF5_15") (pintype "bidirectional"))
    )
    (net (code "133") (name "unconnected-(U0-C-PF10-Pad22)") (class "Default")
      (node (ref "U0-C") (pin "22") (pinfunction "PF10_22") (pintype "bidirectional"))
    )
    (net (code "134") (name "unconnected-(U0-C-PF11-Pad49)") (class "Default")
      (node (ref "U0-C") (pin "49") (pinfunction "PF11_49") (pintype "bidirectional"))
    )
    (net (code "135") (name "unconnected-(U0-C-PF12-Pad50)") (class "Default")
      (node (ref "U0-C") (pin "50") (pinfunction "PF12_50") (pintype "bidirectional"))
    )
    (net (code "136") (name "unconnected-(U0-C-PG2-Pad87)") (class "Default")
      (node (ref "U0-C") (pin "87") (pinfunction "PG2_87") (pintype "bidirectional"))
    )
    (net (code "137") (name "unconnected-(U0-C-PG3-Pad88)") (class "Default")
      (node (ref "U0-C") (pin "88") (pinfunction "PG3_88") (pintype "bidirectional"))
    )
    (net (code "138") (name "unconnected-(U0-C-PG5-Pad90)") (class "Default")
      (node (ref "U0-C") (pin "90") (pinfunction "PG5_90") (pintype "bidirectional"))
    )
    (net (code "139") (name "unconnected-(U0-C-PG6-Pad91)") (class "Default")
      (node (ref "U0-C") (pin "91") (pinfunction "PG6_91") (pintype "bidirectional"))
    )
    (net (code "140") (name "unconnected-(U0-C-PG7-Pad92)") (class "Default")
      (node (ref "U0-C") (pin "92") (pinfunction "PG7_92") (pintype "bidirectional"))
    )
    (net (code "141") (name "unconnected-(U0-C-PG8-Pad93)") (class "Default")
      (node (ref "U0-C") (pin "93") (pinfunction "PG8_93") (pintype "bidirectional"))
    )
    (net (code "142") (name "unconnected-(U0-C-PG9-Pad124)") (class "Default")
      (node (ref "U0-C") (pin "124") (pinfunction "PG9_124") (pintype "bidirectional"))
    )
    (net (code "143") (name "unconnected-(U0-C-PG10-Pad125)") (class "Default")
      (node (ref "U0-C") (pin "125") (pinfunction "PG10_125") (pintype "bidirectional"))
    )
    (net (code "144") (name "unconnected-(U0-C-PG11-Pad126)") (class "Default")
      (node (ref "U0-C") (pin "126") (pinfunction "PG11_126") (pintype "bidirectional"))
    )
    (net (code "145") (name "unconnected-(U0-C-PG12-Pad127)") (class "Default")
      (node (ref "U0-C") (pin "127") (pinfunction "PG12_127") (pintype "bidirectional"))
    )
    (net (code "146") (name "unconnected-(U0-C-PG13-Pad128)") (class "Default")
      (node (ref "U0-C") (pin "128") (pinfunction "PG13_128") (pintype "bidirectional"))
    )
    (net (code "147") (name "unconnected-(U0-C-PG14-Pad129)") (class "Default")
      (node (ref "U0-C") (pin "129") (pinfunction "PG14_129") (pintype "bidirectional"))
    )
    (net (code "148") (name "unconnected-(U0-C-PG15-Pad132)") (class "Default")
      (node (ref "U0-C") (pin "132") (pinfunction "PG15_132") (pintype "bidirectional"))
    )
    (net (code "149") (name "unconnected-(U1-C-EP-Pad9)") (class "Default")
      (node (ref "U1-C") (pin "9") (pinfunction "EP_9") (pintype "bidirectional"))
    )
  )
)
